# 2__FPGA.net
KiCad netlist of a schematic drawn in Altium Designer
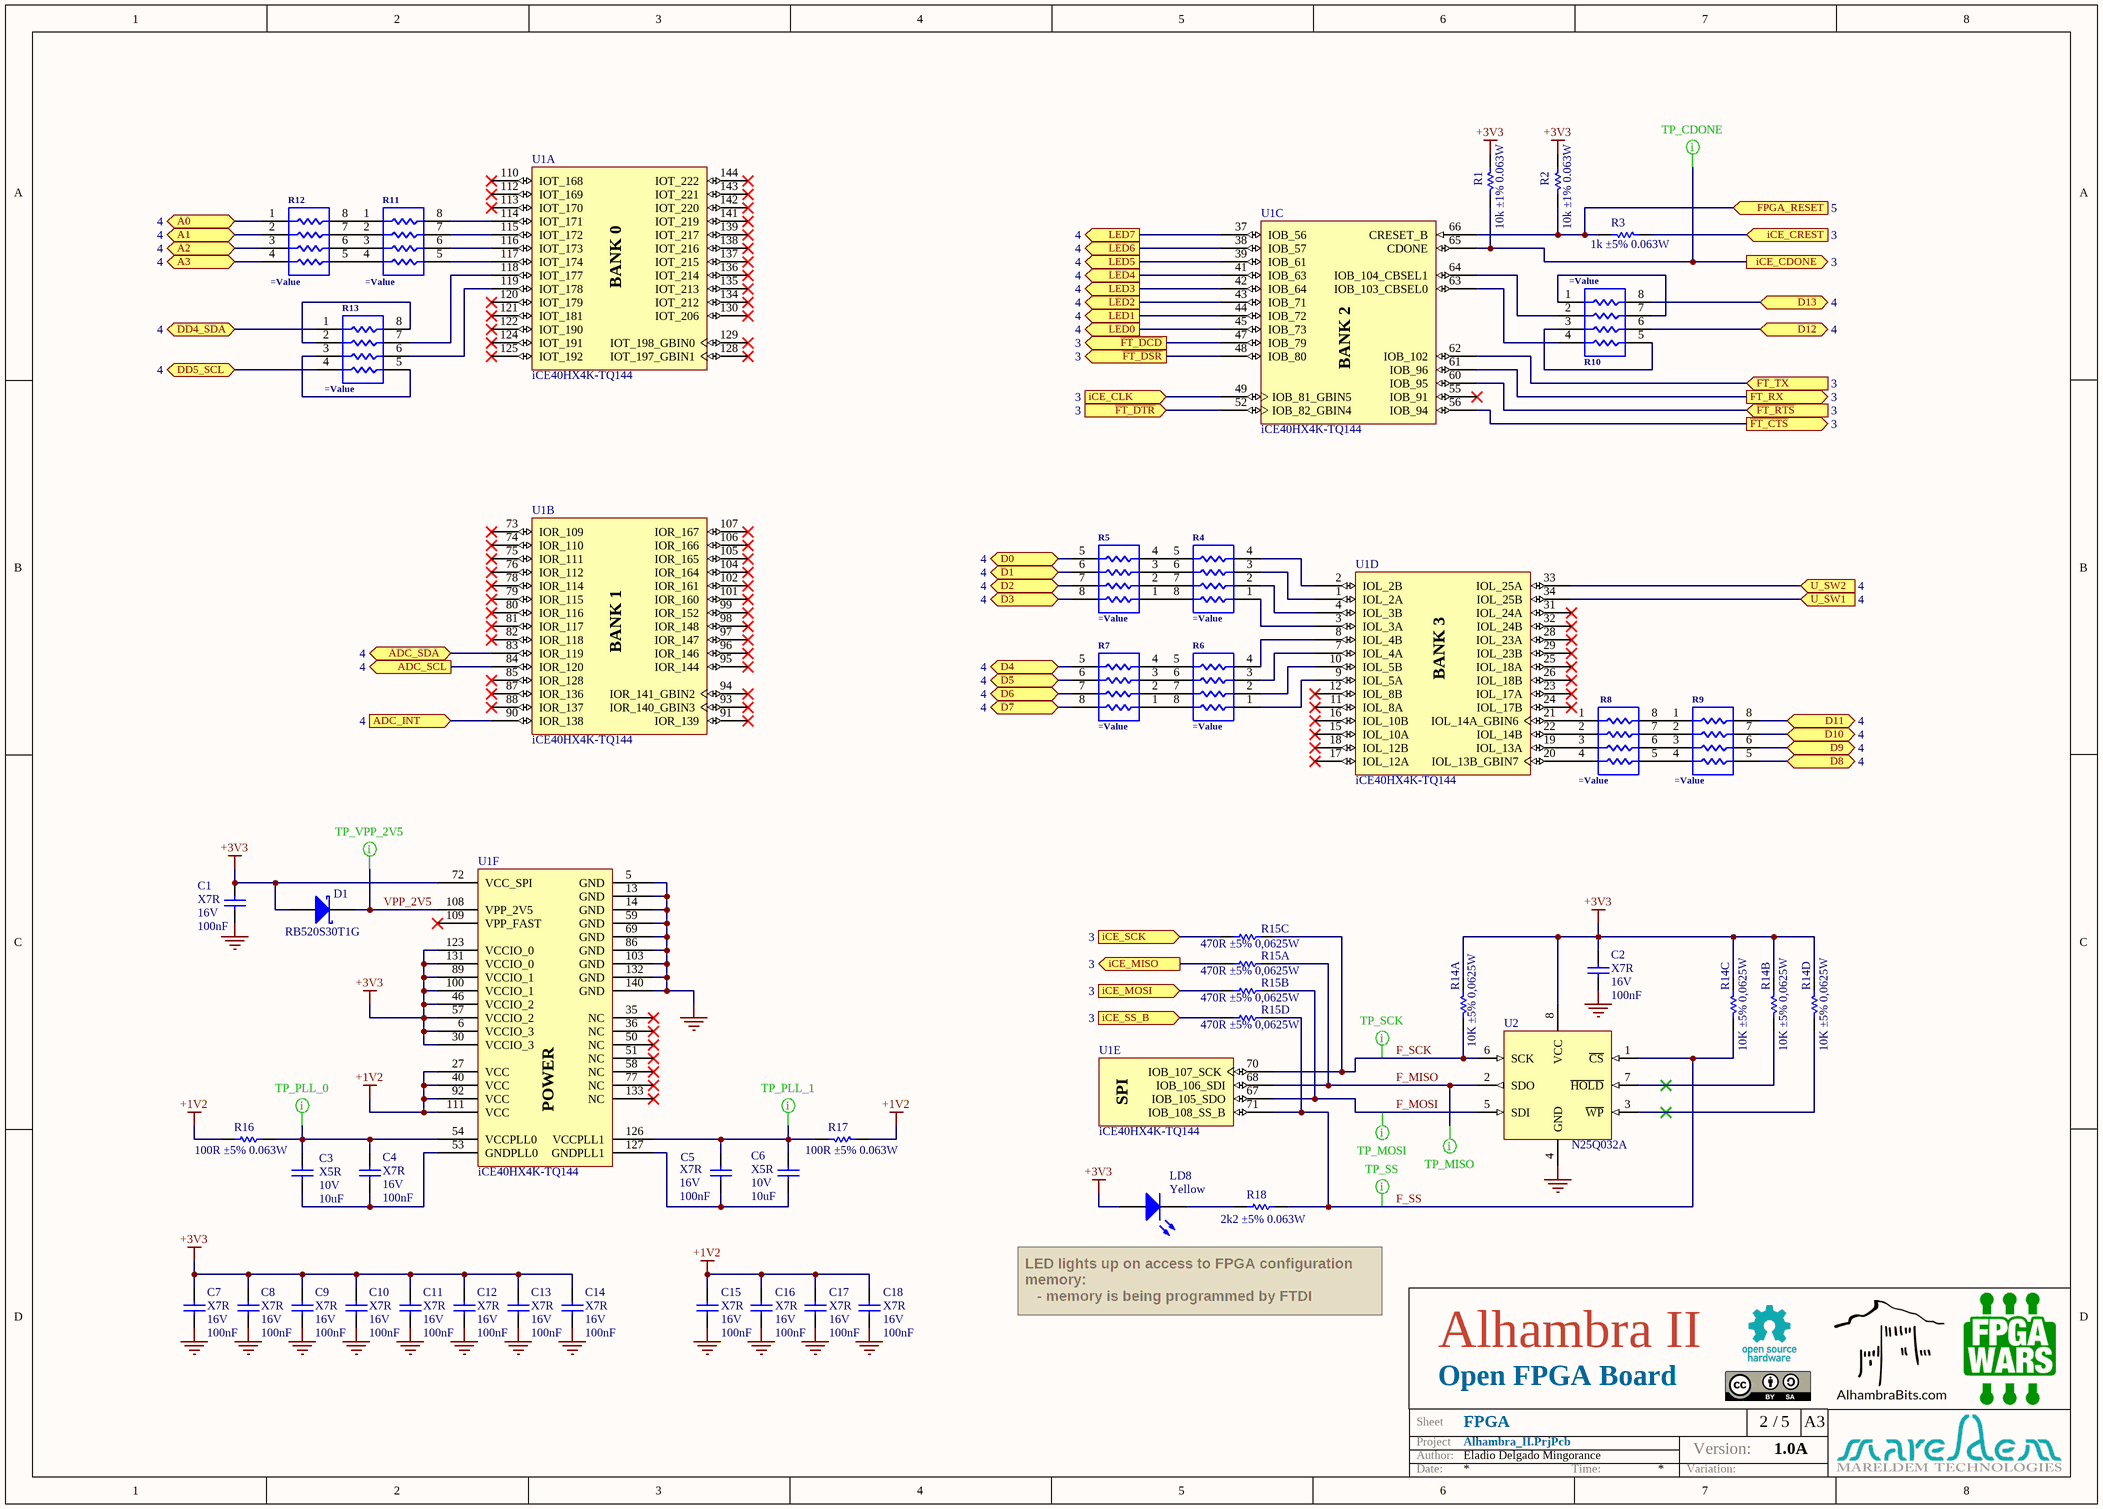
[diagram p0: [2]_FPGA.SchDoc]

(export (version "E")
  (design (tool "Eeschema 10.0.6"))
  (components
    (comp (ref "C1")
      (value "Capacitor")
      (footprint "C0402")
      (description "Capacitor SMD")
      (fields
        (field (name "DIELECTRIC") "X7R")
        (field (name "VOLTAGE") "16V")
        (field (name "CAPACITANCE") "100nF")
        (field (name "PART NUMBER") "C0402_100nF_16V_±10%")
        (field (name "TOLERANCE") "±10%")
      )
      (libsource (lib "Pasives_Capacitor_SMD") (part "Capacitor"))
    )
    (comp (ref "C2")
      (value "Capacitor")
      (footprint "C0402")
      (description "Capacitor SMD")
      (fields
        (field (name "DIELECTRIC") "X7R")
        (field (name "VOLTAGE") "16V")
        (field (name "CAPACITANCE") "100nF")
        (field (name "PART NUMBER") "C0402_100nF_16V_±10%")
        (field (name "TOLERANCE") "±10%")
      )
      (libsource (lib "Pasives_Capacitor_SMD") (part "Capacitor"))
    )
    (comp (ref "C3")
      (value "Capacitor")
      (footprint "C0603")
      (description "Capacitor SMD")
      (fields
        (field (name "DIELECTRIC") "X5R")
        (field (name "VOLTAGE") "10V")
        (field (name "CAPACITANCE") "10uF")
        (field (name "PART NUMBER") "C0603_10uF_10V_±10%")
        (field (name "TOLERANCE") "±10%")
      )
      (libsource (lib "") (part "Capacitor_1"))
    )
    (comp (ref "C4")
      (value "Capacitor")
      (footprint "C0402")
      (description "Capacitor SMD")
      (fields
        (field (name "DIELECTRIC") "X7R")
        (field (name "VOLTAGE") "16V")
        (field (name "CAPACITANCE") "100nF")
        (field (name "PART NUMBER") "C0402_100nF_16V_±10%")
        (field (name "TOLERANCE") "±10%")
      )
      (libsource (lib "Pasives_Capacitor_SMD") (part "Capacitor"))
    )
    (comp (ref "C5")
      (value "Capacitor")
      (footprint "C0402")
      (description "Capacitor SMD")
      (fields
        (field (name "DIELECTRIC") "X7R")
        (field (name "VOLTAGE") "16V")
        (field (name "CAPACITANCE") "100nF")
        (field (name "PART NUMBER") "C0402_100nF_16V_±10%")
        (field (name "TOLERANCE") "±10%")
      )
      (libsource (lib "Pasives_Capacitor_SMD") (part "Capacitor"))
    )
    (comp (ref "C6")
      (value "Capacitor")
      (footprint "C0603")
      (description "Capacitor SMD")
      (fields
        (field (name "DIELECTRIC") "X5R")
        (field (name "VOLTAGE") "10V")
        (field (name "CAPACITANCE") "10uF")
        (field (name "PART NUMBER") "C0603_10uF_10V_±10%")
        (field (name "TOLERANCE") "±10%")
      )
      (libsource (lib "") (part "Capacitor_1"))
    )
    (comp (ref "C7")
      (value "Capacitor")
      (footprint "C0402:C0402")
      (description "Capacitor SMD")
      (fields
        (field (name "DIELECTRIC") "X7R")
        (field (name "VOLTAGE") "16V")
        (field (name "CAPACITANCE") "100nF")
        (field (name "PART NUMBER") "C0402_100nF_16V_±10%")
        (field (name "TOLERANCE") "±10%")
      )
      (libsource (lib "Pasives_Capacitor_SMD") (part "Capacitor"))
    )
    (comp (ref "C8")
      (value "Capacitor")
      (footprint "C0402:C0402")
      (description "Capacitor SMD")
      (fields
        (field (name "DIELECTRIC") "X7R")
        (field (name "VOLTAGE") "16V")
        (field (name "CAPACITANCE") "100nF")
        (field (name "PART NUMBER") "C0402_100nF_16V_±10%")
        (field (name "TOLERANCE") "±10%")
      )
      (libsource (lib "Pasives_Capacitor_SMD") (part "Capacitor"))
    )
    (comp (ref "C9")
      (value "Capacitor")
      (footprint "C0402")
      (description "Capacitor SMD")
      (fields
        (field (name "DIELECTRIC") "X7R")
        (field (name "VOLTAGE") "16V")
        (field (name "CAPACITANCE") "100nF")
        (field (name "PART NUMBER") "C0402_100nF_16V_±10%")
        (field (name "TOLERANCE") "±10%")
      )
      (libsource (lib "Pasives_Capacitor_SMD") (part "Capacitor"))
    )
    (comp (ref "C10")
      (value "Capacitor")
      (footprint "C0402")
      (description "Capacitor SMD")
      (fields
        (field (name "DIELECTRIC") "X7R")
        (field (name "VOLTAGE") "16V")
        (field (name "CAPACITANCE") "100nF")
        (field (name "PART NUMBER") "C0402_100nF_16V_±10%")
        (field (name "TOLERANCE") "±10%")
      )
      (libsource (lib "Pasives_Capacitor_SMD") (part "Capacitor"))
    )
    (comp (ref "C11")
      (value "Capacitor")
      (footprint "C0402")
      (description "Capacitor SMD")
      (fields
        (field (name "DIELECTRIC") "X7R")
        (field (name "VOLTAGE") "16V")
        (field (name "CAPACITANCE") "100nF")
        (field (name "PART NUMBER") "C0402_100nF_16V_±10%")
        (field (name "TOLERANCE") "±10%")
      )
      (libsource (lib "Pasives_Capacitor_SMD") (part "Capacitor"))
    )
    (comp (ref "C12")
      (value "Capacitor")
      (footprint "C0402")
      (description "Capacitor SMD")
      (fields
        (field (name "DIELECTRIC") "X7R")
        (field (name "VOLTAGE") "16V")
        (field (name "CAPACITANCE") "100nF")
        (field (name "PART NUMBER") "C0402_100nF_16V_±10%")
        (field (name "TOLERANCE") "±10%")
      )
      (libsource (lib "Pasives_Capacitor_SMD") (part "Capacitor"))
    )
    (comp (ref "C13")
      (value "Capacitor")
      (footprint "C0402")
      (description "Capacitor SMD")
      (fields
        (field (name "DIELECTRIC") "X7R")
        (field (name "VOLTAGE") "16V")
        (field (name "CAPACITANCE") "100nF")
        (field (name "PART NUMBER") "C0402_100nF_16V_±10%")
        (field (name "TOLERANCE") "±10%")
      )
      (libsource (lib "Pasives_Capacitor_SMD") (part "Capacitor"))
    )
    (comp (ref "C14")
      (value "Capacitor")
      (footprint "C0402")
      (description "Capacitor SMD")
      (fields
        (field (name "DIELECTRIC") "X7R")
        (field (name "VOLTAGE") "16V")
        (field (name "CAPACITANCE") "100nF")
        (field (name "PART NUMBER") "C0402_100nF_16V_±10%")
        (field (name "TOLERANCE") "±10%")
      )
      (libsource (lib "Pasives_Capacitor_SMD") (part "Capacitor"))
    )
    (comp (ref "C15")
      (value "Capacitor")
      (footprint "C0402")
      (description "Capacitor SMD")
      (fields
        (field (name "DIELECTRIC") "X7R")
        (field (name "VOLTAGE") "16V")
        (field (name "CAPACITANCE") "100nF")
        (field (name "PART NUMBER") "C0402_100nF_16V_±10%")
        (field (name "TOLERANCE") "±10%")
      )
      (libsource (lib "Pasives_Capacitor_SMD") (part "Capacitor"))
    )
    (comp (ref "C16")
      (value "Capacitor")
      (footprint "C0402")
      (description "Capacitor SMD")
      (fields
        (field (name "DIELECTRIC") "X7R")
        (field (name "VOLTAGE") "16V")
        (field (name "CAPACITANCE") "100nF")
        (field (name "PART NUMBER") "C0402_100nF_16V_±10%")
        (field (name "TOLERANCE") "±10%")
      )
      (libsource (lib "Pasives_Capacitor_SMD") (part "Capacitor"))
    )
    (comp (ref "C17")
      (value "Capacitor")
      (footprint "C0402")
      (description "Capacitor SMD")
      (fields
        (field (name "DIELECTRIC") "X7R")
        (field (name "VOLTAGE") "16V")
        (field (name "CAPACITANCE") "100nF")
        (field (name "PART NUMBER") "C0402_100nF_16V_±10%")
        (field (name "TOLERANCE") "±10%")
      )
      (libsource (lib "Pasives_Capacitor_SMD") (part "Capacitor"))
    )
    (comp (ref "C18")
      (value "Capacitor")
      (footprint "C0402")
      (description "Capacitor SMD")
      (fields
        (field (name "DIELECTRIC") "X7R")
        (field (name "VOLTAGE") "16V")
        (field (name "CAPACITANCE") "100nF")
        (field (name "PART NUMBER") "C0402_100nF_16V_±10%")
        (field (name "TOLERANCE") "±10%")
      )
      (libsource (lib "Pasives_Capacitor_SMD") (part "Capacitor"))
    )
    (comp (ref "D1")
      (value "RB520S30T1G")
      (footprint "SOD523")
      (description "Schottky Diode")
      (fields (field (name "MANUFACTURER") "On Semiconductor"))
      (libsource (lib "Diodes") (part "Schottky"))
    )
    (comp (ref "LD8")
      (value "Yellow")
      (footprint "LED0603")
      (description "LED")
      (fields (field (name "PART NUMBER") "LED Yellow 0603 Wurth") (field (name "MANUFACTURER") "WE"))
      (libsource (lib "Optoelectronics") (part "LED"))
    )
    (comp (ref "R1")
      (value "10k ±1% 0.063W")
      (footprint "R0402")
      (description "Resistor, SMD")
      (fields (field (name "TOLERANCE") "±1%") (field (name "POWER") "0.063W"))
      (libsource (lib "Pasives_Resistor_SMD") (part "Resistor"))
    )
    (comp (ref "R2")
      (value "10k ±1% 0.063W")
      (footprint "R0402")
      (description "Resistor, SMD")
      (fields (field (name "TOLERANCE") "±1%") (field (name "POWER") "0.063W"))
      (libsource (lib "Pasives_Resistor_SMD") (part "Resistor"))
    )
    (comp (ref "R3")
      (value "1k ±5% 0.063W")
      (footprint "R0402")
      (description "Resistor, SMD")
      (fields (field (name "TOLERANCE") "±5%") (field (name "POWER") "0.063W"))
      (libsource (lib "Pasives_Resistor_SMD") (part "Resistor"))
    )
    (comp (ref "R4")
      (value "~")
      (footprint "4xArray_1206_Convex")
      (description "Resistor, Array 4x1")
      (fields
        (field (name "PART NUMBER") "4xArray_1206_Convex_100R_0,0625W_0,05")
        (field (name "POWER") "0,0625W")
      )
      (libsource (lib "Pasives_Resistor_SMD") (part "Resistor_4x"))
    )
    (comp (ref "R5")
      (value "~")
      (footprint "4xArray_1206_Convex")
      (description "Resistor, Array 4x1")
      (fields
        (field (name "PART NUMBER") "4xArray_1206_Convex_100R_0,0625W_0,05")
        (field (name "POWER") "0,0625W")
      )
      (libsource (lib "Pasives_Resistor_SMD") (part "Resistor_4x"))
    )
    (comp (ref "R6")
      (value "~")
      (footprint "4xArray_1206_Convex")
      (description "Resistor, Array 4x1")
      (fields
        (field (name "PART NUMBER") "4xArray_1206_Convex_100R_0,0625W_0,05")
        (field (name "POWER") "0,0625W")
      )
      (libsource (lib "Pasives_Resistor_SMD") (part "Resistor_4x"))
    )
    (comp (ref "R7")
      (value "~")
      (footprint "4xArray_1206_Convex")
      (description "Resistor, Array 4x1")
      (fields
        (field (name "PART NUMBER") "4xArray_1206_Convex_100R_0,0625W_0,05")
        (field (name "POWER") "0,0625W")
      )
      (libsource (lib "Pasives_Resistor_SMD") (part "Resistor_4x"))
    )
    (comp (ref "R8")
      (value "~")
      (footprint "4xArray_1206_Convex")
      (description "Resistor, Array 4x1")
      (fields
        (field (name "PART NUMBER") "4xArray_1206_Convex_100R_0,0625W_0,05")
        (field (name "POWER") "0,0625W")
      )
      (libsource (lib "Pasives_Resistor_SMD") (part "Resistor_4x"))
    )
    (comp (ref "R9")
      (value "~")
      (footprint "4xArray_1206_Convex")
      (description "Resistor, Array 4x1")
      (fields
        (field (name "PART NUMBER") "4xArray_1206_Convex_100R_0,0625W_0,05")
        (field (name "POWER") "0,0625W")
      )
      (libsource (lib "Pasives_Resistor_SMD") (part "Resistor_4x"))
    )
    (comp (ref "R10")
      (value "~")
      (footprint "4xArray_1206_Convex")
      (description "Resistor, Array 4x1")
      (fields
        (field (name "PART NUMBER") "4xArray_1206_Convex_100R_0,0625W_0,05")
        (field (name "POWER") "0,0625W")
      )
      (libsource (lib "Pasives_Resistor_SMD") (part "Resistor_4x"))
    )
    (comp (ref "R11")
      (value "~")
      (footprint "4xArray_1206_Convex")
      (description "Resistor, Array 4x1")
      (fields
        (field (name "PART NUMBER") "4xArray_1206_Convex_100R_0,0625W_0,05")
        (field (name "POWER") "0,0625W")
      )
      (libsource (lib "Pasives_Resistor_SMD") (part "Resistor_4x"))
    )
    (comp (ref "R12")
      (value "~")
      (footprint "4xArray_1206_Convex")
      (description "Resistor, Array 4x1")
      (fields
        (field (name "PART NUMBER") "4xArray_1206_Convex_100R_0,0625W_0,05")
        (field (name "POWER") "0,0625W")
      )
      (libsource (lib "Pasives_Resistor_SMD") (part "Resistor_4x"))
    )
    (comp (ref "R13")
      (value "~")
      (footprint "4xArray_1206_Convex")
      (description "Resistor, Array 4x1")
      (fields
        (field (name "PART NUMBER") "4xArray_1206_Convex_100R_0,0625W_0,05")
        (field (name "POWER") "0,0625W")
      )
      (libsource (lib "Pasives_Resistor_SMD") (part "Resistor_4x"))
    )
    (comp (ref "R14")
      (value "10K ±5% 0,0625W")
      (footprint "4xArray_1206_Convex")
      (description "Resistor")
      (fields (field (name "TOLERANCE") "±5%") (field (name "POWER") "0,0625W"))
      (libsource (lib "Pasives_Resistor_SMD") (part "Resistor_x4_Parts"))
    )
    (comp (ref "R15")
      (value "470R ±5% 0,0625W")
      (footprint "4xArray_1206_Convex")
      (description "Resistor")
      (fields (field (name "TOLERANCE") "±5%") (field (name "POWER") "0,0625W"))
      (libsource (lib "Pasives_Resistor_SMD") (part "Resistor_x4_Parts"))
    )
    (comp (ref "R16")
      (value "100R ±5% 0.063W")
      (footprint "R0402")
      (description "Resistor, SMD")
      (fields (field (name "TOLERANCE") "±5%") (field (name "POWER") "0.063W"))
      (libsource (lib "Pasives_Resistor_SMD") (part "Resistor"))
    )
    (comp (ref "R17")
      (value "100R ±5% 0.063W")
      (footprint "R0402")
      (description "Resistor, SMD")
      (fields (field (name "TOLERANCE") "±5%") (field (name "POWER") "0.063W"))
      (libsource (lib "Pasives_Resistor_SMD") (part "Resistor"))
    )
    (comp (ref "R18")
      (value "2k2 ±5% 0.063W")
      (footprint "R0402")
      (description "Resistor, SMD")
      (fields (field (name "TOLERANCE") "±5%") (field (name "POWER") "0.063W"))
      (libsource (lib "Pasives_Resistor_SMD") (part "Resistor"))
    )
    (comp (ref "U1")
      (value "iCE40HX4K-TQ144")
      (footprint "TQFP-144_IPC-MD_HX1K")
      (fields (field (name "PART NUMBER") "iCE40-HX4K") (field (name "MANUFACTURER") "Lattice"))
      (libsource (lib "") (part "iCE40HX4K-TQ144_1"))
    )
    (comp (ref "U2")
      (value "N25Q032A")
      (footprint "DFN-8 6x5mm")
      (description "NOR Flash Memory, serial")
      (fields (field (name "MANUFACTURER") "Micron"))
      (libsource (lib "Memory_Serial") (part "N25Q032A"))
    )
  )
  (nets
    (net (code "1") (name "+1V2") (class "Default")
      (node (ref "C15") (pin "2") (pinfunction "2_2") (pintype "passive"))
      (node (ref "C16") (pin "2") (pinfunction "2_2") (pintype "passive"))
      (node (ref "C17") (pin "2") (pinfunction "2_2") (pintype "passive"))
      (node (ref "C18") (pin "2") (pinfunction "2_2") (pintype "passive"))
      (node (ref "R16") (pin "2") (pinfunction "2_2") (pintype "passive"))
      (node (ref "R17") (pin "2") (pinfunction "2_2") (pintype "passive"))
      (node (ref "U1") (pin "111") (pinfunction "VCC_111") (pintype "power_in"))
      (node (ref "U1") (pin "27") (pinfunction "VCC_27") (pintype "power_in"))
      (node (ref "U1") (pin "40") (pinfunction "VCC_40") (pintype "power_in"))
      (node (ref "U1") (pin "92") (pinfunction "VCC_92") (pintype "power_in"))
    )
    (net (code "2") (name "+3V3") (class "Default")
      (node (ref "C1") (pin "2") (pinfunction "2_2") (pintype "passive"))
      (node (ref "C10") (pin "2") (pinfunction "2_2") (pintype "passive"))
      (node (ref "C11") (pin "2") (pinfunction "2_2") (pintype "passive"))
      (node (ref "C12") (pin "2") (pinfunction "2_2") (pintype "passive"))
      (node (ref "C13") (pin "2") (pinfunction "2_2") (pintype "passive"))
      (node (ref "C14") (pin "2") (pinfunction "2_2") (pintype "passive"))
      (node (ref "C2") (pin "1") (pinfunction "1_1") (pintype "passive"))
      (node (ref "C7") (pin "2") (pinfunction "2_2") (pintype "passive"))
      (node (ref "C8") (pin "2") (pinfunction "2_2") (pintype "passive"))
      (node (ref "C9") (pin "2") (pinfunction "2_2") (pintype "passive"))
      (node (ref "D1") (pin "A") (pinfunction "A_A") (pintype "passive"))
      (node (ref "LD8") (pin "A") (pinfunction "A_A") (pintype "passive"))
      (node (ref "R1") (pin "1") (pinfunction "1_1") (pintype "passive"))
      (node (ref "R14") (pin "1") (pinfunction "1_1") (pintype "passive"))
      (node (ref "R14") (pin "2") (pinfunction "2_2") (pintype "passive"))
      (node (ref "R14") (pin "3") (pinfunction "3_3") (pintype "passive"))
      (node (ref "R14") (pin "4") (pinfunction "4_4") (pintype "passive"))
      (node (ref "R2") (pin "1") (pinfunction "1_1") (pintype "passive"))
      (node (ref "U1") (pin "100") (pinfunction "VCCIO_1_100") (pintype "power_in"))
      (node (ref "U1") (pin "123") (pinfunction "VCCIO_0_123") (pintype "power_in"))
      (node (ref "U1") (pin "131") (pinfunction "VCCIO_0_131") (pintype "power_in"))
      (node (ref "U1") (pin "30") (pinfunction "VCCIO_3_30") (pintype "power_in"))
      (node (ref "U1") (pin "46") (pinfunction "VCCIO_2_46") (pintype "power_in"))
      (node (ref "U1") (pin "57") (pinfunction "VCCIO_2_57") (pintype "power_in"))
      (node (ref "U1") (pin "6") (pinfunction "VCCIO_3_6") (pintype "power_in"))
      (node (ref "U1") (pin "72") (pinfunction "VCC_SPI_72") (pintype "power_in"))
      (node (ref "U1") (pin "89") (pinfunction "VCCIO_1_89") (pintype "power_in"))
      (node (ref "U2") (pin "8") (pinfunction "VCC_8") (pintype "power_in"))
    )
    (net (code "3") (name "/A0") (class "Default")
      (node (ref "R12") (pin "1") (pinfunction "1_1") (pintype "passive"))
    )
    (net (code "4") (name "/A1") (class "Default")
      (node (ref "R12") (pin "2") (pinfunction "2_2") (pintype "passive"))
    )
    (net (code "5") (name "/A2") (class "Default")
      (node (ref "R12") (pin "3") (pinfunction "3_3") (pintype "passive"))
    )
    (net (code "6") (name "/A3") (class "Default")
      (node (ref "R12") (pin "4") (pinfunction "4_4") (pintype "passive"))
    )
    (net (code "7") (name "/ADC_INT") (class "Default")
      (node (ref "U1") (pin "90") (pinfunction "IOR_138_90") (pintype "bidirectional"))
    )
    (net (code "8") (name "/ADC_SCL") (class "Default")
      (node (ref "U1") (pin "84") (pinfunction "IOR_120_84") (pintype "bidirectional"))
    )
    (net (code "9") (name "/ADC_SDA") (class "Default")
      (node (ref "U1") (pin "83") (pinfunction "IOR_119_83") (pintype "bidirectional"))
    )
    (net (code "10") (name "/D0") (class "Default")
      (node (ref "R5") (pin "5") (pinfunction "5_5") (pintype "passive"))
    )
    (net (code "11") (name "/D1") (class "Default")
      (node (ref "R5") (pin "6") (pinfunction "6_6") (pintype "passive"))
    )
    (net (code "12") (name "/D2") (class "Default")
      (node (ref "R5") (pin "7") (pinfunction "7_7") (pintype "passive"))
    )
    (net (code "13") (name "/D3") (class "Default")
      (node (ref "R5") (pin "8") (pinfunction "8_8") (pintype "passive"))
    )
    (net (code "14") (name "/D4") (class "Default")
      (node (ref "R7") (pin "5") (pinfunction "5_5") (pintype "passive"))
    )
    (net (code "15") (name "/D5") (class "Default")
      (node (ref "R7") (pin "6") (pinfunction "6_6") (pintype "passive"))
    )
    (net (code "16") (name "/D6") (class "Default")
      (node (ref "R7") (pin "7") (pinfunction "7_7") (pintype "passive"))
    )
    (net (code "17") (name "/D7") (class "Default")
      (node (ref "R7") (pin "8") (pinfunction "8_8") (pintype "passive"))
    )
    (net (code "18") (name "/D8") (class "Default")
      (node (ref "R9") (pin "5") (pinfunction "5_5") (pintype "passive"))
    )
    (net (code "19") (name "/D9") (class "Default")
      (node (ref "R9") (pin "6") (pinfunction "6_6") (pintype "passive"))
    )
    (net (code "20") (name "/D10") (class "Default")
      (node (ref "R9") (pin "7") (pinfunction "7_7") (pintype "passive"))
    )
    (net (code "21") (name "/D11") (class "Default")
      (node (ref "R9") (pin "8") (pinfunction "8_8") (pintype "passive"))
    )
    (net (code "22") (name "/D12") (class "Default")
      (node (ref "R10") (pin "6") (pinfunction "6_6") (pintype "passive"))
    )
    (net (code "23") (name "/D13") (class "Default")
      (node (ref "R10") (pin "8") (pinfunction "8_8") (pintype "passive"))
    )
    (net (code "24") (name "/DD4_SDA") (class "Default")
      (node (ref "R13") (pin "1") (pinfunction "1_1") (pintype "passive"))
    )
    (net (code "25") (name "/DD5_SCL") (class "Default")
      (node (ref "R13") (pin "4") (pinfunction "4_4") (pintype "passive"))
    )
    (net (code "26") (name "/FPGA_RESET") (class "Default")
      (node (ref "R2") (pin "2") (pinfunction "2_2") (pintype "passive"))
      (node (ref "R3") (pin "2") (pinfunction "2_2") (pintype "passive"))
      (node (ref "U1") (pin "66") (pinfunction "CRESET_B_66") (pintype "input"))
    )
    (net (code "27") (name "/FT_CTS") (class "Default")
      (node (ref "U1") (pin "56") (pinfunction "IOB_94_56") (pintype "bidirectional"))
    )
    (net (code "28") (name "/FT_DCD") (class "Default")
      (node (ref "U1") (pin "47") (pinfunction "IOB_79_47") (pintype "bidirectional"))
    )
    (net (code "29") (name "/FT_DSR") (class "Default")
      (node (ref "U1") (pin "48") (pinfunction "IOB_80_48") (pintype "bidirectional"))
    )
    (net (code "30") (name "/FT_DTR") (class "Default")
      (node (ref "U1") (pin "52") (pinfunction "IOB_82_GBIN4_52") (pintype "bidirectional"))
    )
    (net (code "31") (name "/FT_RTS") (class "Default")
      (node (ref "U1") (pin "60") (pinfunction "IOB_95_60") (pintype "bidirectional"))
    )
    (net (code "32") (name "/FT_RX") (class "Default")
      (node (ref "U1") (pin "61") (pinfunction "IOB_96_61") (pintype "bidirectional"))
    )
    (net (code "33") (name "/FT_TX") (class "Default")
      (node (ref "U1") (pin "62") (pinfunction "IOB_102_62") (pintype "bidirectional"))
    )
    (net (code "34") (name "/F_MISO") (class "Default")
      (node (ref "R15") (pin "8") (pinfunction "8_8") (pintype "passive"))
      (node (ref "U1") (pin "68") (pinfunction "IOB_45_SDI_68") (pintype "bidirectional"))
      (node (ref "U2") (pin "2") (pinfunction "SDO_2") (pintype "output"))
    )
    (net (code "35") (name "/F_MOSI") (class "Default")
      (node (ref "R15") (pin "7") (pinfunction "7_7") (pintype "passive"))
      (node (ref "U1") (pin "67") (pinfunction "IOB_44_SDO_67") (pintype "bidirectional"))
      (node (ref "U2") (pin "5") (pinfunction "SDI_5") (pintype "input"))
    )
    (net (code "36") (name "/F_SCK") (class "Default")
      (node (ref "R14") (pin "8") (pinfunction "8_8") (pintype "passive"))
      (node (ref "R15") (pin "6") (pinfunction "6_6") (pintype "passive"))
      (node (ref "U1") (pin "70") (pinfunction "IOB_46_SCK_70") (pintype "bidirectional"))
      (node (ref "U2") (pin "6") (pinfunction "SCK_6") (pintype "input"))
    )
    (net (code "37") (name "/F_SS") (class "Default")
      (node (ref "R14") (pin "6") (pinfunction "6_6") (pintype "passive"))
      (node (ref "R15") (pin "5") (pinfunction "5_5") (pintype "passive"))
      (node (ref "R18") (pin "2") (pinfunction "2_2") (pintype "passive"))
      (node (ref "U1") (pin "71") (pinfunction "IOB_47_SS_B_71") (pintype "bidirectional"))
      (node (ref "U2") (pin "1") (pinfunction "CS_1") (pintype "input"))
    )
    (net (code "38") (name "/LED0") (class "Default")
      (node (ref "U1") (pin "45") (pinfunction "IOB_73_45") (pintype "bidirectional"))
    )
    (net (code "39") (name "/LED1") (class "Default")
      (node (ref "U1") (pin "44") (pinfunction "IOB_72_44") (pintype "bidirectional"))
    )
    (net (code "40") (name "/LED2") (class "Default")
      (node (ref "U1") (pin "43") (pinfunction "IOB_71_43") (pintype "bidirectional"))
    )
    (net (code "41") (name "/LED3") (class "Default")
      (node (ref "U1") (pin "42") (pinfunction "IOB_64_42") (pintype "bidirectional"))
    )
    (net (code "42") (name "/LED4") (class "Default")
      (node (ref "U1") (pin "41") (pinfunction "IOB_63_41") (pintype "bidirectional"))
    )
    (net (code "43") (name "/LED5") (class "Default")
      (node (ref "U1") (pin "39") (pinfunction "IOB_61_39") (pintype "bidirectional"))
    )
    (net (code "44") (name "/LED6") (class "Default")
      (node (ref "U1") (pin "38") (pinfunction "IOB_57_38") (pintype "bidirectional"))
    )
    (net (code "45") (name "/LED7") (class "Default")
      (node (ref "U1") (pin "37") (pinfunction "IOB_56_37") (pintype "bidirectional"))
    )
    (net (code "46") (name "/U_SW1") (class "Default")
      (node (ref "U1") (pin "34") (pinfunction "IOL_25B_34") (pintype "bidirectional"))
    )
    (net (code "47") (name "/U_SW2") (class "Default")
      (node (ref "U1") (pin "33") (pinfunction "IOL_25A_33") (pintype "bidirectional"))
    )
    (net (code "48") (name "/VPP_2V5") (class "Default")
      (node (ref "D1") (pin "k") (pinfunction "K_k") (pintype "passive"))
      (node (ref "U1") (pin "108") (pinfunction "VPP_2V5_108") (pintype "power_in"))
    )
    (net (code "49") (name "/iCE_CDONE") (class "Default")
      (node (ref "R1") (pin "2") (pinfunction "2_2") (pintype "passive"))
      (node (ref "U1") (pin "65") (pinfunction "CDONE_65") (pintype "bidirectional"))
    )
    (net (code "50") (name "/iCE_CLK") (class "Default")
      (node (ref "U1") (pin "49") (pinfunction "IOB_81_GBIN5_49") (pintype "bidirectional"))
    )
    (net (code "51") (name "/iCE_CREST") (class "Default")
      (node (ref "R3") (pin "1") (pinfunction "1_1") (pintype "passive"))
    )
    (net (code "52") (name "/iCE_MISO") (class "Default")
      (node (ref "R15") (pin "1") (pinfunction "1_1") (pintype "passive"))
    )
    (net (code "53") (name "/iCE_MOSI") (class "Default")
      (node (ref "R15") (pin "2") (pinfunction "2_2") (pintype "passive"))
    )
    (net (code "54") (name "/iCE_SCK") (class "Default")
      (node (ref "R15") (pin "3") (pinfunction "3_3") (pintype "passive"))
    )
    (net (code "55") (name "/iCE_SS_B") (class "Default")
      (node (ref "R15") (pin "4") (pinfunction "4_4") (pintype "passive"))
    )
    (net (code "56") (name "GND") (class "Default")
      (node (ref "C1") (pin "1") (pinfunction "1_1") (pintype "passive"))
      (node (ref "C10") (pin "1") (pinfunction "1_1") (pintype "passive"))
      (node (ref "C11") (pin "1") (pinfunction "1_1") (pintype "passive"))
      (node (ref "C12") (pin "1") (pinfunction "1_1") (pintype "passive"))
      (node (ref "C13") (pin "1") (pinfunction "1_1") (pintype "passive"))
      (node (ref "C14") (pin "1") (pinfunction "1_1") (pintype "passive"))
      (node (ref "C15") (pin "1") (pinfunction "1_1") (pintype "passive"))
      (node (ref "C16") (pin "1") (pinfunction "1_1") (pintype "passive"))
      (node (ref "C17") (pin "1") (pinfunction "1_1") (pintype "passive"))
      (node (ref "C18") (pin "1") (pinfunction "1_1") (pintype "passive"))
      (node (ref "C2") (pin "2") (pinfunction "2_2") (pintype "passive"))
      (node (ref "C7") (pin "1") (pinfunction "1_1") (pintype "passive"))
      (node (ref "C8") (pin "1") (pinfunction "1_1") (pintype "passive"))
      (node (ref "C9") (pin "1") (pinfunction "1_1") (pintype "passive"))
      (node (ref "U1") (pin "103") (pinfunction "GND_103") (pintype "power_in"))
      (node (ref "U1") (pin "13") (pinfunction "GND_13") (pintype "power_in"))
      (node (ref "U1") (pin "132") (pinfunction "GND_132") (pintype "power_in"))
      (node (ref "U1") (pin "14") (pinfunction "GND_14") (pintype "power_in"))
      (node (ref "U1") (pin "140") (pinfunction "GND_140") (pintype "power_in"))
      (node (ref "U1") (pin "5") (pinfunction "GND_5") (pintype "power_in"))
      (node (ref "U1") (pin "59") (pinfunction "GND_59") (pintype "power_in"))
      (node (ref "U1") (pin "69") (pinfunction "GND_69") (pintype "power_in"))
      (node (ref "U1") (pin "86") (pinfunction "GND_86") (pintype "power_in"))
      (node (ref "U2") (pin "4") (pinfunction "GND_4") (pintype "power_in"))
    )
    (net (code "57") (name "Net-(LD8-PadK)") (class "Default")
      (node (ref "LD8") (pin "K") (pinfunction "K_K") (pintype "passive"))
      (node (ref "R18") (pin "1") (pinfunction "1_1") (pintype "passive"))
    )
    (net (code "58") (name "Net-(R4-Pad5)") (class "Default")
      (node (ref "R4") (pin "5") (pinfunction "5_5") (pintype "passive"))
      (node (ref "R5") (pin "4") (pinfunction "4_4") (pintype "passive"))
    )
    (net (code "59") (name "Net-(R4-Pad6)") (class "Default")
      (node (ref "R4") (pin "6") (pinfunction "6_6") (pintype "passive"))
      (node (ref "R5") (pin "3") (pinfunction "3_3") (pintype "passive"))
    )
    (net (code "60") (name "Net-(R4-Pad7)") (class "Default")
      (node (ref "R4") (pin "7") (pinfunction "7_7") (pintype "passive"))
      (node (ref "R5") (pin "2") (pinfunction "2_2") (pintype "passive"))
    )
    (net (code "61") (name "Net-(R4-Pad8)") (class "Default")
      (node (ref "R4") (pin "8") (pinfunction "8_8") (pintype "passive"))
      (node (ref "R5") (pin "1") (pinfunction "1_1") (pintype "passive"))
    )
    (net (code "62") (name "Net-(R6-Pad5)") (class "Default")
      (node (ref "R6") (pin "5") (pinfunction "5_5") (pintype "passive"))
      (node (ref "R7") (pin "4") (pinfunction "4_4") (pintype "passive"))
    )
    (net (code "63") (name "Net-(R6-Pad6)") (class "Default")
      (node (ref "R6") (pin "6") (pinfunction "6_6") (pintype "passive"))
      (node (ref "R7") (pin "3") (pinfunction "3_3") (pintype "passive"))
    )
    (net (code "64") (name "Net-(R6-Pad7)") (class "Default")
      (node (ref "R6") (pin "7") (pinfunction "7_7") (pintype "passive"))
      (node (ref "R7") (pin "2") (pinfunction "2_2") (pintype "passive"))
    )
    (net (code "65") (name "Net-(R6-Pad8)") (class "Default")
      (node (ref "R6") (pin "8") (pinfunction "8_8") (pintype "passive"))
      (node (ref "R7") (pin "1") (pinfunction "1_1") (pintype "passive"))
    )
    (net (code "66") (name "Net-(R8-Pad5)") (class "Default")
      (node (ref "R8") (pin "5") (pinfunction "5_5") (pintype "passive"))
      (node (ref "R9") (pin "4") (pinfunction "4_4") (pintype "passive"))
    )
    (net (code "67") (name "Net-(R8-Pad6)") (class "Default")
      (node (ref "R8") (pin "6") (pinfunction "6_6") (pintype "passive"))
      (node (ref "R9") (pin "3") (pinfunction "3_3") (pintype "passive"))
    )
    (net (code "68") (name "Net-(R8-Pad7)") (class "Default")
      (node (ref "R8") (pin "7") (pinfunction "7_7") (pintype "passive"))
      (node (ref "R9") (pin "2") (pinfunction "2_2") (pintype "passive"))
    )
    (net (code "69") (name "Net-(R8-Pad8)") (class "Default")
      (node (ref "R8") (pin "8") (pinfunction "8_8") (pintype "passive"))
      (node (ref "R9") (pin "1") (pinfunction "1_1") (pintype "passive"))
    )
    (net (code "70") (name "Net-(R10-Pad1)") (class "Default")
      (node (ref "R10") (pin "1") (pinfunction "1_1") (pintype "passive"))
      (node (ref "R10") (pin "7") (pinfunction "7_7") (pintype "passive"))
    )
    (net (code "71") (name "Net-(R10-Pad3)") (class "Default")
      (node (ref "R10") (pin "3") (pinfunction "3_3") (pintype "passive"))
      (node (ref "R10") (pin "5") (pinfunction "5_5") (pintype "passive"))
    )
    (net (code "72") (name "Net-(R11-Pad1)") (class "Default")
      (node (ref "R11") (pin "1") (pinfunction "1_1") (pintype "passive"))
      (node (ref "R12") (pin "8") (pinfunction "8_8") (pintype "passive"))
    )
    (net (code "73") (name "Net-(R11-Pad2)") (class "Default")
      (node (ref "R11") (pin "2") (pinfunction "2_2") (pintype "passive"))
      (node (ref "R12") (pin "7") (pinfunction "7_7") (pintype "passive"))
    )
    (net (code "74") (name "Net-(R11-Pad3)") (class "Default")
      (node (ref "R11") (pin "3") (pinfunction "3_3") (pintype "passive"))
      (node (ref "R12") (pin "6") (pinfunction "6_6") (pintype "passive"))
    )
    (net (code "75") (name "Net-(R11-Pad4)") (class "Default")
      (node (ref "R11") (pin "4") (pinfunction "4_4") (pintype "passive"))
      (node (ref "R12") (pin "5") (pinfunction "5_5") (pintype "passive"))
    )
    (net (code "76") (name "Net-(R13-Pad2)") (class "Default")
      (node (ref "R13") (pin "2") (pinfunction "2_2") (pintype "passive"))
      (node (ref "R13") (pin "8") (pinfunction "8_8") (pintype "passive"))
    )
    (net (code "77") (name "Net-(R13-Pad3)") (class "Default")
      (node (ref "R13") (pin "3") (pinfunction "3_3") (pintype "passive"))
      (node (ref "R13") (pin "5") (pinfunction "5_5") (pintype "passive"))
    )
    (net (code "78") (name "Net-(U1A-IOT_171)") (class "Default")
      (node (ref "R11") (pin "8") (pinfunction "8_8") (pintype "passive"))
      (node (ref "U1") (pin "114") (pinfunction "IOT_171_114") (pintype "bidirectional"))
    )
    (net (code "79") (name "Net-(U1A-IOT_172)") (class "Default")
      (node (ref "R11") (pin "7") (pinfunction "7_7") (pintype "passive"))
      (node (ref "U1") (pin "115") (pinfunction "IOT_172_115") (pintype "bidirectional"))
    )
    (net (code "80") (name "Net-(U1A-IOT_173)") (class "Default")
      (node (ref "R11") (pin "6") (pinfunction "6_6") (pintype "passive"))
      (node (ref "U1") (pin "116") (pinfunction "IOT_173_116") (pintype "bidirectional"))
    )
    (net (code "81") (name "Net-(U1A-IOT_174)") (class "Default")
      (node (ref "R11") (pin "5") (pinfunction "5_5") (pintype "passive"))
      (node (ref "U1") (pin "117") (pinfunction "IOT_174_117") (pintype "bidirectional"))
    )
    (net (code "82") (name "Net-(U1A-IOT_177)") (class "Default")
      (node (ref "R13") (pin "7") (pinfunction "7_7") (pintype "passive"))
      (node (ref "U1") (pin "118") (pinfunction "IOT_177_118") (pintype "bidirectional"))
    )
    (net (code "83") (name "Net-(U1A-IOT_178)") (class "Default")
      (node (ref "R13") (pin "6") (pinfunction "6_6") (pintype "passive"))
      (node (ref "U1") (pin "119") (pinfunction "IOT_178_119") (pintype "bidirectional"))
    )
    (net (code "84") (name "Net-(U1C-IOB_103_CBSEL0)") (class "Default")
      (node (ref "R10") (pin "4") (pinfunction "4_4") (pintype "passive"))
      (node (ref "U1") (pin "63") (pinfunction "IOB_103_CBSEL0_63") (pintype "bidirectional"))
    )
    (net (code "85") (name "Net-(U1C-IOB_104_CBSEL1)") (class "Default")
      (node (ref "R10") (pin "2") (pinfunction "2_2") (pintype "passive"))
      (node (ref "U1") (pin "64") (pinfunction "IOB_104_CBSEL1_64") (pintype "bidirectional"))
    )
    (net (code "86") (name "Net-(U1D-IOL_2A)") (class "Default")
      (node (ref "R4") (pin "3") (pinfunction "3_3") (pintype "passive"))
      (node (ref "U1") (pin "1") (pinfunction "IOL_2A_1") (pintype "bidirectional"))
    )
    (net (code "87") (name "Net-(U1D-IOL_2B)") (class "Default")
      (node (ref "R4") (pin "4") (pinfunction "4_4") (pintype "passive"))
      (node (ref "U1") (pin "2") (pinfunction "IOL_2B_2") (pintype "bidirectional"))
    )
    (net (code "88") (name "Net-(U1D-IOL_3A)") (class "Default")
      (node (ref "R4") (pin "1") (pinfunction "1_1") (pintype "passive"))
      (node (ref "U1") (pin "3") (pinfunction "IOL_3A_3") (pintype "bidirectional"))
    )
    (net (code "89") (name "Net-(U1D-IOL_3B)") (class "Default")
      (node (ref "R4") (pin "2") (pinfunction "2_2") (pintype "passive"))
      (node (ref "U1") (pin "4") (pinfunction "IOL_3B_4") (pintype "bidirectional"))
    )
    (net (code "90") (name "Net-(U1D-IOL_4A)") (class "Default")
      (node (ref "R6") (pin "3") (pinfunction "3_3") (pintype "passive"))
      (node (ref "U1") (pin "7") (pinfunction "IOL_4A_7") (pintype "bidirectional"))
    )
    (net (code "91") (name "Net-(U1D-IOL_4B)") (class "Default")
      (node (ref "R6") (pin "4") (pinfunction "4_4") (pintype "passive"))
      (node (ref "U1") (pin "8") (pinfunction "IOL_4B_8") (pintype "bidirectional"))
    )
    (net (code "92") (name "Net-(U1D-IOL_5A)") (class "Default")
      (node (ref "R6") (pin "1") (pinfunction "1_1") (pintype "passive"))
      (node (ref "U1") (pin "9") (pinfunction "IOL_5A_9") (pintype "bidirectional"))
    )
    (net (code "93") (name "Net-(U1D-IOL_5B)") (class "Default")
      (node (ref "R6") (pin "2") (pinfunction "2_2") (pintype "passive"))
      (node (ref "U1") (pin "10") (pinfunction "IOL_5B_10") (pintype "bidirectional"))
    )
    (net (code "94") (name "Net-(U1D-IOL_13A)") (class "Default")
      (node (ref "R8") (pin "3") (pinfunction "3_3") (pintype "passive"))
      (node (ref "U1") (pin "19") (pinfunction "IOL_13A_19") (pintype "bidirectional"))
    )
    (net (code "95") (name "Net-(U1D-IOL_13B_GBIN7)") (class "Default")
      (node (ref "R8") (pin "4") (pinfunction "4_4") (pintype "passive"))
      (node (ref "U1") (pin "20") (pinfunction "IOL_13B_GBIN7_20") (pintype "bidirectional"))
    )
    (net (code "96") (name "Net-(U1D-IOL_14A_GBIN6)") (class "Default")
      (node (ref "R8") (pin "1") (pinfunction "1_1") (pintype "passive"))
      (node (ref "U1") (pin "21") (pinfunction "IOL_14A_GBIN6_21") (pintype "bidirectional"))
    )
    (net (code "97") (name "Net-(U1D-IOL_14B)") (class "Default")
      (node (ref "R8") (pin "2") (pinfunction "2_2") (pintype "passive"))
      (node (ref "U1") (pin "22") (pinfunction "IOL_14B_22") (pintype "bidirectional"))
    )
    (net (code "98") (name "Net-(U1F-GNDPLL0)") (class "Default")
      (node (ref "C3") (pin "2") (pinfunction "2_2") (pintype "passive"))
      (node (ref "C4") (pin "1") (pinfunction "1_1") (pintype "passive"))
      (node (ref "U1") (pin "53") (pinfunction "GNDPLL0_53") (pintype "power_in"))
    )
    (net (code "99") (name "Net-(U1F-GNDPLL1)") (class "Default")
      (node (ref "C5") (pin "1") (pinfunction "1_1") (pintype "passive"))
      (node (ref "C6") (pin "1") (pinfunction "1_1") (pintype "passive"))
      (node (ref "U1") (pin "127") (pinfunction "GNDPLL1_127") (pintype "power_in"))
    )
    (net (code "100") (name "Net-(U1F-VCCPLL0)") (class "Default")
      (node (ref "C3") (pin "1") (pinfunction "1_1") (pintype "passive"))
      (node (ref "C4") (pin "2") (pinfunction "2_2") (pintype "passive"))
      (node (ref "R16") (pin "1") (pinfunction "1_1") (pintype "passive"))
      (node (ref "U1") (pin "54") (pinfunction "VCCPLL0_54") (pintype "power_in"))
    )
    (net (code "101") (name "Net-(U1F-VCCPLL1)") (class "Default")
      (node (ref "C5") (pin "2") (pinfunction "2_2") (pintype "passive"))
      (node (ref "C6") (pin "2") (pinfunction "2_2") (pintype "passive"))
      (node (ref "R17") (pin "1") (pinfunction "1_1") (pintype "passive"))
      (node (ref "U1") (pin "126") (pinfunction "VCCPLL1_126") (pintype "power_in"))
    )
    (net (code "102") (name "Net-(U2-HOLD)") (class "Default")
      (node (ref "R14") (pin "7") (pinfunction "7_7") (pintype "passive"))
      (node (ref "U2") (pin "7") (pinfunction "HOLD_7") (pintype "input"))
    )
    (net (code "103") (name "Net-(U2-WP)") (class "Default")
      (node (ref "R14") (pin "5") (pinfunction "5_5") (pintype "passive"))
      (node (ref "U2") (pin "3") (pinfunction "WP_3") (pintype "input"))
    )
    (net (code "104") (name "unconnected-(U1A-IOT_168-Pad110)") (class "Default")
      (node (ref "U1") (pin "110") (pinfunction "IOT_168_110") (pintype "bidirectional+no_connect"))
    )
    (net (code "105") (name "unconnected-(U1A-IOT_169-Pad112)") (class "Default")
      (node (ref "U1") (pin "112") (pinfunction "IOT_169_112") (pintype "bidirectional+no_connect"))
    )
    (net (code "106") (name "unconnected-(U1A-IOT_170-Pad113)") (class "Default")
      (node (ref "U1") (pin "113") (pinfunction "IOT_170_113") (pintype "bidirectional+no_connect"))
    )
    (net (code "107") (name "unconnected-(U1A-IOT_179-Pad120)") (class "Default")
      (node (ref "U1") (pin "120") (pinfunction "IOT_179_120") (pintype "bidirectional+no_connect"))
    )
    (net (code "108") (name "unconnected-(U1A-IOT_181-Pad121)") (class "Default")
      (node (ref "U1") (pin "121") (pinfunction "IOT_181_121") (pintype "bidirectional+no_connect"))
    )
    (net (code "109") (name "unconnected-(U1A-IOT_190-Pad122)") (class "Default")
      (node (ref "U1") (pin "122") (pinfunction "IOT_190_122") (pintype "bidirectional+no_connect"))
    )
    (net (code "110") (name "unconnected-(U1A-IOT_191-Pad124)") (class "Default")
      (node (ref "U1") (pin "124") (pinfunction "IOT_191_124") (pintype "bidirectional+no_connect"))
    )
    (net (code "111") (name "unconnected-(U1A-IOT_192-Pad125)") (class "Default")
      (node (ref "U1") (pin "125") (pinfunction "IOT_192_125") (pintype "bidirectional+no_connect"))
    )
    (net (code "112") (name "unconnected-(U1A-IOT_197_GBIN1-Pad128)") (class "Default")
      (node (ref "U1") (pin "128") (pinfunction "IOT_197_GBIN1_128") (pintype "bidirectional+no_connect"))
    )
    (net (code "113") (name "unconnected-(U1A-IOT_198_GBIN0-Pad129)") (class "Default")
      (node (ref "U1") (pin "129") (pinfunction "IOT_198_GBIN0_129") (pintype "bidirectional+no_connect"))
    )
    (net (code "114") (name "unconnected-(U1A-IOT_206-Pad130)") (class "Default")
      (node (ref "U1") (pin "130") (pinfunction "IOT_206_130") (pintype "bidirectional+no_connect"))
    )
    (net (code "115") (name "unconnected-(U1A-IOT_212-Pad134)") (class "Default")
      (node (ref "U1") (pin "134") (pinfunction "IOT_212_134") (pintype "bidirectional+no_connect"))
    )
    (net (code "116") (name "unconnected-(U1A-IOT_213-Pad135)") (class "Default")
      (node (ref "U1") (pin "135") (pinfunction "IOT_213_135") (pintype "bidirectional+no_connect"))
    )
    (net (code "117") (name "unconnected-(U1A-IOT_214-Pad136)") (class "Default")
      (node (ref "U1") (pin "136") (pinfunction "IOT_214_136") (pintype "bidirectional+no_connect"))
    )
    (net (code "118") (name "unconnected-(U1A-IOT_215-Pad137)") (class "Default")
      (node (ref "U1") (pin "137") (pinfunction "IOT_215_137") (pintype "bidirectional+no_connect"))
    )
    (net (code "119") (name "unconnected-(U1A-IOT_216-Pad138)") (class "Default")
      (node (ref "U1") (pin "138") (pinfunction "IOT_216_138") (pintype "bidirectional+no_connect"))
    )
    (net (code "120") (name "unconnected-(U1A-IOT_217-Pad139)") (class "Default")
      (node (ref "U1") (pin "139") (pinfunction "IOT_217_139") (pintype "bidirectional+no_connect"))
    )
    (net (code "121") (name "unconnected-(U1A-IOT_219-Pad141)") (class "Default")
      (node (ref "U1") (pin "141") (pinfunction "IOT_219_141") (pintype "bidirectional+no_connect"))
    )
    (net (code "122") (name "unconnected-(U1A-IOT_220-Pad142)") (class "Default")
      (node (ref "U1") (pin "142") (pinfunction "IOT_220_142") (pintype "bidirectional+no_connect"))
    )
    (net (code "123") (name "unconnected-(U1A-IOT_221-Pad143)") (class "Default")
      (node (ref "U1") (pin "143") (pinfunction "IOT_221_143") (pintype "bidirectional+no_connect"))
    )
    (net (code "124") (name "unconnected-(U1A-IOT_222-Pad144)") (class "Default")
      (node (ref "U1") (pin "144") (pinfunction "IOT_222_144") (pintype "bidirectional+no_connect"))
    )
    (net (code "125") (name "unconnected-(U1B-IOR_109-Pad73)") (class "Default")
      (node (ref "U1") (pin "73") (pinfunction "IOR_109_73") (pintype "bidirectional+no_connect"))
    )
    (net (code "126") (name "unconnected-(U1B-IOR_110-Pad74)") (class "Default")
      (node (ref "U1") (pin "74") (pinfunction "IOR_110_74") (pintype "bidirectional+no_connect"))
    )
    (net (code "127") (name "unconnected-(U1B-IOR_111-Pad75)") (class "Default")
      (node (ref "U1") (pin "75") (pinfunction "IOR_111_75") (pintype "bidirectional+no_connect"))
    )
    (net (code "128") (name "unconnected-(U1B-IOR_112-Pad76)") (class "Default")
      (node (ref "U1") (pin "76") (pinfunction "IOR_112_76") (pintype "bidirectional+no_connect"))
    )
    (net (code "129") (name "unconnected-(U1B-IOR_114-Pad78)") (class "Default")
      (node (ref "U1") (pin "78") (pinfunction "IOR_114_78") (pintype "bidirectional+no_connect"))
    )
    (net (code "130") (name "unconnected-(U1B-IOR_115-Pad79)") (class "Default")
      (node (ref "U1") (pin "79") (pinfunction "IOR_115_79") (pintype "bidirectional+no_connect"))
    )
    (net (code "131") (name "unconnected-(U1B-IOR_116-Pad80)") (class "Default")
      (node (ref "U1") (pin "80") (pinfunction "IOR_116_80") (pintype "bidirectional+no_connect"))
    )
    (net (code "132") (name "unconnected-(U1B-IOR_117-Pad81)") (class "Default")
      (node (ref "U1") (pin "81") (pinfunction "IOR_117_81") (pintype "bidirectional+no_connect"))
    )
    (net (code "133") (name "unconnected-(U1B-IOR_118-Pad82)") (class "Default")
      (node (ref "U1") (pin "82") (pinfunction "IOR_118_82") (pintype "bidirectional+no_connect"))
    )
    (net (code "134") (name "unconnected-(U1B-IOR_128-Pad85)") (class "Default")
      (node (ref "U1") (pin "85") (pinfunction "IOR_128_85") (pintype "bidirectional+no_connect"))
    )
    (net (code "135") (name "unconnected-(U1B-IOR_136-Pad87)") (class "Default")
      (node (ref "U1") (pin "87") (pinfunction "IOR_136_87") (pintype "bidirectional+no_connect"))
    )
    (net (code "136") (name "unconnected-(U1B-IOR_137-Pad88)") (class "Default")
      (node (ref "U1") (pin "88") (pinfunction "IOR_137_88") (pintype "bidirectional+no_connect"))
    )
    (net (code "137") (name "unconnected-(U1B-IOR_139-Pad91)") (class "Default")
      (node (ref "U1") (pin "91") (pinfunction "IOR_139_91") (pintype "bidirectional+no_connect"))
    )
    (net (code "138") (name "unconnected-(U1B-IOR_140_GBIN3-Pad93)") (class "Default")
      (node (ref "U1") (pin "93") (pinfunction "IOR_140_GBIN3_93") (pintype "bidirectional+no_connect"))
    )
    (net (code "139") (name "unconnected-(U1B-IOR_141_GBIN2-Pad94)") (class "Default")
      (node (ref "U1") (pin "94") (pinfunction "IOR_141_GBIN2_94") (pintype "bidirectional+no_connect"))
    )
    (net (code "140") (name "unconnected-(U1B-IOR_144-Pad95)") (class "Default")
      (node (ref "U1") (pin "95") (pinfunction "IOR_144_95") (pintype "bidirectional+no_connect"))
    )
    (net (code "141") (name "unconnected-(U1B-IOR_146-Pad96)") (class "Default")
      (node (ref "U1") (pin "96") (pinfunction "IOR_146_96") (pintype "bidirectional+no_connect"))
    )
    (net (code "142") (name "unconnected-(U1B-IOR_147-Pad97)") (class "Default")
      (node (ref "U1") (pin "97") (pinfunction "IOR_147_97") (pintype "bidirectional+no_connect"))
    )
    (net (code "143") (name "unconnected-(U1B-IOR_148-Pad98)") (class "Default")
      (node (ref "U1") (pin "98") (pinfunction "IOR_148_98") (pintype "bidirectional+no_connect"))
    )
    (net (code "144") (name "unconnected-(U1B-IOR_152-Pad99)") (class "Default")
      (node (ref "U1") (pin "99") (pinfunction "IOR_152_99") (pintype "bidirectional+no_connect"))
    )
    (net (code "145") (name "unconnected-(U1B-IOR_160-Pad101)") (class "Default")
      (node (ref "U1") (pin "101") (pinfunction "IOR_160_101") (pintype "bidirectional+no_connect"))
    )
    (net (code "146") (name "unconnected-(U1B-IOR_161-Pad102)") (class "Default")
      (node (ref "U1") (pin "102") (pinfunction "IOR_161_102") (pintype "bidirectional+no_connect"))
    )
    (net (code "147") (name "unconnected-(U1B-IOR_164-Pad104)") (class "Default")
      (node (ref "U1") (pin "104") (pinfunction "IOR_164_104") (pintype "bidirectional+no_connect"))
    )
    (net (code "148") (name "unconnected-(U1B-IOR_165-Pad105)") (class "Default")
      (node (ref "U1") (pin "105") (pinfunction "IOR_165_105") (pintype "bidirectional+no_connect"))
    )
    (net (code "149") (name "unconnected-(U1B-IOR_166-Pad106)") (class "Default")
      (node (ref "U1") (pin "106") (pinfunction "IOR_166_106") (pintype "bidirectional+no_connect"))
    )
    (net (code "150") (name "unconnected-(U1B-IOR_167-Pad107)") (class "Default")
      (node (ref "U1") (pin "107") (pinfunction "IOR_167_107") (pintype "bidirectional+no_connect"))
    )
    (net (code "151") (name "unconnected-(U1C-IOB_91-Pad55)") (class "Default")
      (node (ref "U1") (pin "55") (pinfunction "IOB_91_55") (pintype "bidirectional+no_connect"))
    )
    (net (code "152") (name "unconnected-(U1D-IOL_8A-Pad11)") (class "Default")
      (node (ref "U1") (pin "11") (pinfunction "IOL_8A_11") (pintype "bidirectional+no_connect"))
    )
    (net (code "153") (name "unconnected-(U1D-IOL_8B-Pad12)") (class "Default")
      (node (ref "U1") (pin "12") (pinfunction "IOL_8B_12") (pintype "bidirectional+no_connect"))
    )
    (net (code "154") (name "unconnected-(U1D-IOL_10A-Pad15)") (class "Default")
      (node (ref "U1") (pin "15") (pinfunction "IOL_10A_15") (pintype "bidirectional+no_connect"))
    )
    (net (code "155") (name "unconnected-(U1D-IOL_10B-Pad16)") (class "Default")
      (node (ref "U1") (pin "16") (pinfunction "IOL_10B_16") (pintype "bidirectional+no_connect"))
    )
    (net (code "156") (name "unconnected-(U1D-IOL_12A-Pad17)") (class "Default")
      (node (ref "U1") (pin "17") (pinfunction "IOL_12A_17") (pintype "bidirectional+no_connect"))
    )
    (net (code "157") (name "unconnected-(U1D-IOL_12B-Pad18)") (class "Default")
      (node (ref "U1") (pin "18") (pinfunction "IOL_12B_18") (pintype "bidirectional+no_connect"))
    )
    (net (code "158") (name "unconnected-(U1D-IOL_17A-Pad23)") (class "Default")
      (node (ref "U1") (pin "23") (pinfunction "IOL_17A_23") (pintype "bidirectional+no_connect"))
    )
    (net (code "159") (name "unconnected-(U1D-IOL_17B-Pad24)") (class "Default")
      (node (ref "U1") (pin "24") (pinfunction "IOL_17B_24") (pintype "bidirectional+no_connect"))
    )
    (net (code "160") (name "unconnected-(U1D-IOL_18A-Pad25)") (class "Default")
      (node (ref "U1") (pin "25") (pinfunction "IOL_18A_25") (pintype "bidirectional+no_connect"))
    )
    (net (code "161") (name "unconnected-(U1D-IOL_18B-Pad26)") (class "Default")
      (node (ref "U1") (pin "26") (pinfunction "IOL_18B_26") (pintype "bidirectional+no_connect"))
    )
    (net (code "162") (name "unconnected-(U1D-IOL_23A-Pad28)") (class "Default")
      (node (ref "U1") (pin "28") (pinfunction "IOL_23A_28") (pintype "bidirectional+no_connect"))
    )
    (net (code "163") (name "unconnected-(U1D-IOL_23B-Pad29)") (class "Default")
      (node (ref "U1") (pin "29") (pinfunction "IOL_23B_29") (pintype "bidirectional+no_connect"))
    )
    (net (code "164") (name "unconnected-(U1D-IOL_24A-Pad31)") (class "Default")
      (node (ref "U1") (pin "31") (pinfunction "IOL_24A_31") (pintype "bidirectional+no_connect"))
    )
    (net (code "165") (name "unconnected-(U1D-IOL_24B-Pad32)") (class "Default")
      (node (ref "U1") (pin "32") (pinfunction "IOL_24B_32") (pintype "bidirectional+no_connect"))
    )
    (net (code "166") (name "unconnected-(U1F-NC-Pad35)") (class "Default")
      (node (ref "U1") (pin "35") (pinfunction "NC_35") (pintype "passive+no_connect"))
    )
    (net (code "167") (name "unconnected-(U1F-NC-Pad36)") (class "Default")
      (node (ref "U1") (pin "36") (pinfunction "NC_36") (pintype "passive+no_connect"))
    )
    (net (code "168") (name "unconnected-(U1F-NC-Pad50)") (class "Default")
      (node (ref "U1") (pin "50") (pinfunction "NC_50") (pintype "passive+no_connect"))
    )
    (net (code "169") (name "unconnected-(U1F-NC-Pad51)") (class "Default")
      (node (ref "U1") (pin "51") (pinfunction "NC_51") (pintype "passive+no_connect"))
    )
    (net (code "170") (name "unconnected-(U1F-NC-Pad58)") (class "Default")
      (node (ref "U1") (pin "58") (pinfunction "NC_58") (pintype "passive+no_connect"))
    )
    (net (code "171") (name "unconnected-(U1F-NC-Pad77)") (class "Default")
      (node (ref "U1") (pin "77") (pinfunction "NC_77") (pintype "passive+no_connect"))
    )
    (net (code "172") (name "unconnected-(U1F-NC-Pad133)") (class "Default")
      (node (ref "U1") (pin "133") (pinfunction "NC_133") (pintype "passive+no_connect"))
    )
    (net (code "173") (name "unconnected-(U1F-VPP_FAST-Pad109)") (class "Default")
      (node (ref "U1") (pin "109") (pinfunction "VPP_FAST_109") (pintype "power_in+no_connect"))
    )
  )
)
